# esp8266-rgb-ledstrip.net
KiCad netlist of a schematic drawn in EAGLE
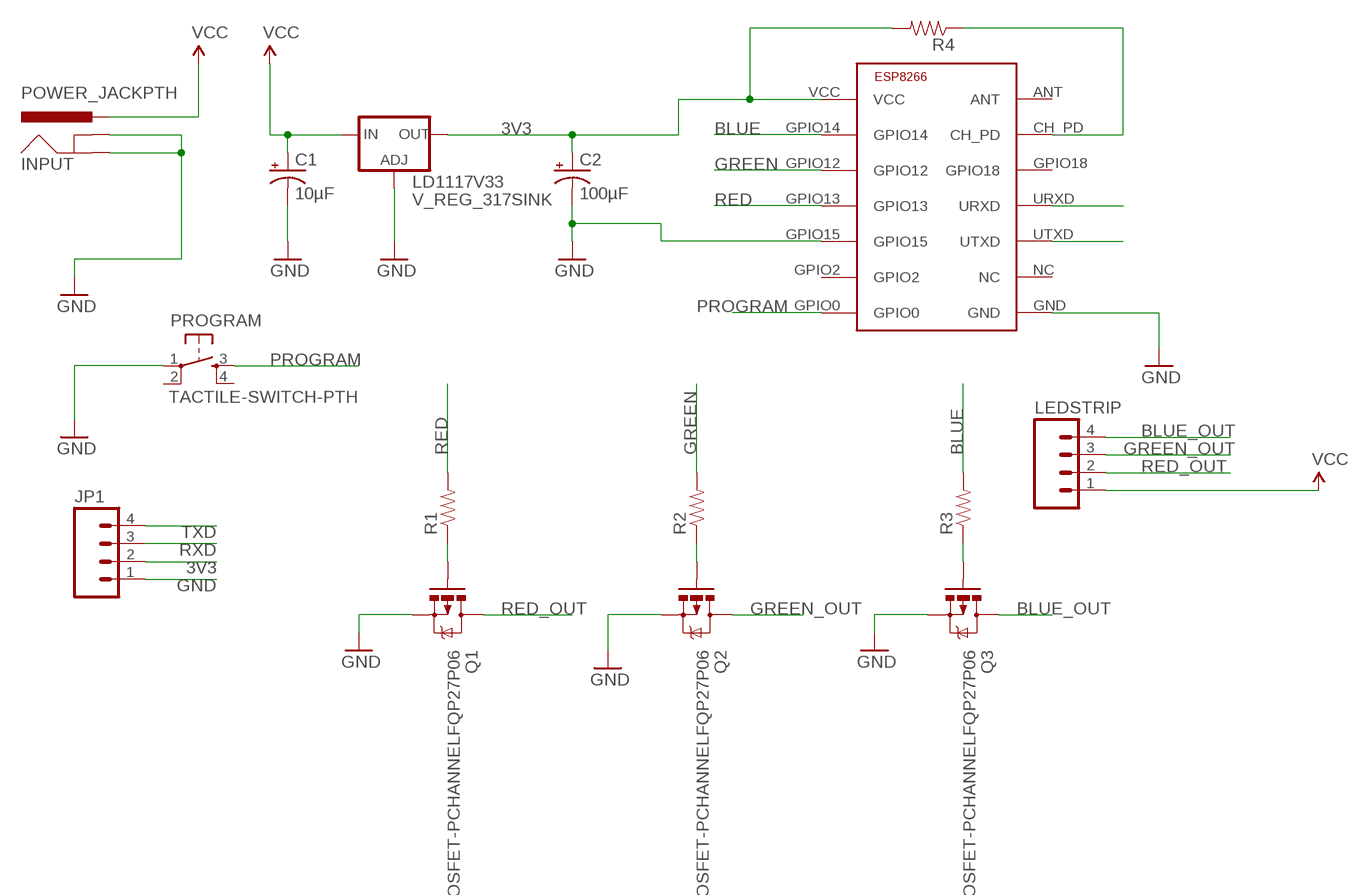
[diagram p0: schematic, sheet 1]

(export (version "E")
  (design (tool "Eeschema 10.0.6"))
  (components
    (comp (ref "C1")
      (value "10µF")
      (footprint "eagle-import:CPOL-RADIAL-10UF-25V")
      (libsource (lib "eagle-import") (part "CAP_POLPTH2"))
    )
    (comp (ref "C2")
      (value "100µF")
      (footprint "eagle-import:CPOL-RADIAL-100UF-25V")
      (libsource (lib "eagle-import") (part "CAP_POLPTH1"))
    )
    (comp (ref "INPUT")
      (value "POWER_JACKPTH")
      (footprint "eagle-import:POWER_JACK_PTH")
      (libsource (lib "eagle-import") (part "POWER_JACKPTH"))
    )
    (comp (ref "JP1")
      (value "M04PTH")
      (footprint "eagle-import:1X04")
      (libsource (lib "eagle-import") (part "M04PTH"))
    )
    (comp (ref "LD1117V33")
      (value "V_REG_317SINK")
      (footprint "eagle-import:TO220-ADJ")
      (libsource (lib "eagle-import") (part "V_REG_317SINK"))
    )
    (comp (ref "LEDSTRIP")
      (value "M04PTH")
      (footprint "eagle-import:1X04")
      (libsource (lib "eagle-import") (part "M04PTH"))
    )
    (comp (ref "PROGRAM")
      (value "TACTILE-SWITCH-PTH")
      (footprint "eagle-import:TAC-SWITCH-PTH")
      (libsource (lib "eagle-import") (part "TACTILE-SWITCH-PTH"))
    )
    (comp (ref "Q1")
      (value "MOSFET-PCHANNELFQP27P06")
      (footprint "eagle-import:TO220V")
      (libsource (lib "eagle-import") (part "MOSFET-PCHANNELFQP27P06"))
    )
    (comp (ref "Q2")
      (value "MOSFET-PCHANNELFQP27P06")
      (footprint "eagle-import:TO220V")
      (libsource (lib "eagle-import") (part "MOSFET-PCHANNELFQP27P06"))
    )
    (comp (ref "Q3")
      (value "MOSFET-PCHANNELFQP27P06")
      (footprint "eagle-import:TO220V")
      (libsource (lib "eagle-import") (part "MOSFET-PCHANNELFQP27P06"))
    )
    (comp (ref "R1")
      (value "RESISTORAXIAL-0.3")
      (footprint "eagle-import:AXIAL-0.3")
      (libsource (lib "eagle-import") (part "RESISTORAXIAL-0.3"))
    )
    (comp (ref "R2")
      (value "RESISTORAXIAL-0.3")
      (footprint "eagle-import:AXIAL-0.3")
      (libsource (lib "eagle-import") (part "RESISTORAXIAL-0.3"))
    )
    (comp (ref "R3")
      (value "RESISTORAXIAL-0.3")
      (footprint "eagle-import:AXIAL-0.3")
      (libsource (lib "eagle-import") (part "RESISTORAXIAL-0.3"))
    )
    (comp (ref "R4")
      (value "RESISTORAXIAL-0.3")
      (footprint "eagle-import:AXIAL-0.3")
      (libsource (lib "eagle-import") (part "RESISTORAXIAL-0.3"))
    )
    (comp (ref "U$1")
      (value "ESP8266-03")
      (footprint "eagle-import:ESP-03")
      (libsource (lib "eagle-import") (part "ESP8266-03"))
    )
  )
  (nets
    (net (code "1") (name "/3V3") (class "Default")
      (node (ref "C2") (pin "1") (pinfunction "+_1") (pintype "passive"))
      (node (ref "JP1") (pin "2") (pinfunction "2_2") (pintype "passive"))
      (node (ref "LD1117V33") (pin "OUT") (pinfunction "OUT_OUT") (pintype "output"))
      (node (ref "R4") (pin "P$2") (pinfunction "2_P$2") (pintype "passive"))
      (node (ref "U$1") (pin "VCC") (pinfunction "VCC_VCC") (pintype "bidirectional"))
    )
    (net (code "2") (name "/BLUE") (class "Default")
      (node (ref "R3") (pin "P$2") (pinfunction "2_P$2") (pintype "passive"))
      (node (ref "U$1") (pin "GPIO14") (pinfunction "GPIO14_GPIO14") (pintype "bidirectional"))
    )
    (net (code "3") (name "/BLUE_OUT") (class "Default")
      (node (ref "LEDSTRIP") (pin "4") (pinfunction "4_4") (pintype "passive"))
      (node (ref "Q3") (pin "2") (pinfunction "D_2") (pintype "passive"))
    )
    (net (code "4") (name "/GREEN") (class "Default")
      (node (ref "R2") (pin "P$2") (pinfunction "2_P$2") (pintype "passive"))
      (node (ref "U$1") (pin "GPIO12") (pinfunction "GPIO12_GPIO12") (pintype "bidirectional"))
    )
    (net (code "5") (name "/GREEN_OUT") (class "Default")
      (node (ref "LEDSTRIP") (pin "3") (pinfunction "3_3") (pintype "passive"))
      (node (ref "Q2") (pin "2") (pinfunction "D_2") (pintype "passive"))
    )
    (net (code "6") (name "/PROGRAM") (class "Default")
      (node (ref "PROGRAM") (pin "3") (pinfunction "3_3") (pintype "passive"))
      (node (ref "U$1") (pin "GPIO0") (pinfunction "GPIO0_GPIO0") (pintype "bidirectional"))
    )
    (net (code "7") (name "/RED") (class "Default")
      (node (ref "R1") (pin "P$2") (pinfunction "2_P$2") (pintype "passive"))
      (node (ref "U$1") (pin "GPIO13") (pinfunction "GPIO13_GPIO13") (pintype "bidirectional"))
    )
    (net (code "8") (name "/RED_OUT") (class "Default")
      (node (ref "LEDSTRIP") (pin "2") (pinfunction "2_2") (pintype "passive"))
      (node (ref "Q1") (pin "2") (pinfunction "D_2") (pintype "passive"))
    )
    (net (code "9") (name "/RXD") (class "Default")
      (node (ref "JP1") (pin "3") (pinfunction "3_3") (pintype "passive"))
      (node (ref "U$1") (pin "URXD") (pinfunction "URXD_URXD") (pintype "bidirectional"))
    )
    (net (code "10") (name "/TXD") (class "Default")
      (node (ref "JP1") (pin "4") (pinfunction "4_4") (pintype "passive"))
      (node (ref "U$1") (pin "UTXD") (pinfunction "UTXD_UTXD") (pintype "bidirectional"))
    )
    (net (code "11") (name "GND") (class "Default")
      (node (ref "C1") (pin "2") (pinfunction "-_2") (pintype "passive"))
      (node (ref "C2") (pin "2") (pinfunction "-_2") (pintype "passive"))
      (node (ref "INPUT") (pin "GND") (pinfunction "GND_GND") (pintype "bidirectional"))
      (node (ref "INPUT") (pin "GNDBREAK") (pinfunction "GNDBREAK_GNDBREAK") (pintype "bidirectional"))
      (node (ref "JP1") (pin "1") (pinfunction "1_1") (pintype "passive"))
      (node (ref "LD1117V33") (pin "ADJ") (pinfunction "ADJ_ADJ") (pintype "input"))
      (node (ref "PROGRAM") (pin "1") (pinfunction "1_1") (pintype "passive"))
      (node (ref "Q1") (pin "3") (pinfunction "S_3") (pintype "passive"))
      (node (ref "Q2") (pin "3") (pinfunction "S_3") (pintype "passive"))
      (node (ref "Q3") (pin "3") (pinfunction "S_3") (pintype "passive"))
      (node (ref "U$1") (pin "GND") (pinfunction "GND_GND") (pintype "bidirectional"))
      (node (ref "U$1") (pin "GPIO15") (pinfunction "GPIO15_GPIO15") (pintype "bidirectional"))
    )
    (net (code "12") (name "Net-(Q1-G)") (class "Default")
      (node (ref "Q1") (pin "1") (pinfunction "G_1") (pintype "passive"))
      (node (ref "R1") (pin "P$1") (pinfunction "1_P$1") (pintype "passive"))
    )
    (net (code "13") (name "Net-(Q2-G)") (class "Default")
      (node (ref "Q2") (pin "1") (pinfunction "G_1") (pintype "passive"))
      (node (ref "R2") (pin "P$1") (pinfunction "1_P$1") (pintype "passive"))
    )
    (net (code "14") (name "Net-(Q3-G)") (class "Default")
      (node (ref "Q3") (pin "1") (pinfunction "G_1") (pintype "passive"))
      (node (ref "R3") (pin "P$1") (pinfunction "1_P$1") (pintype "passive"))
    )
    (net (code "15") (name "Net-(R4-1)") (class "Default")
      (node (ref "R4") (pin "P$1") (pinfunction "1_P$1") (pintype "passive"))
      (node (ref "U$1") (pin "CH_PD") (pinfunction "CH_PD_CH_PD") (pintype "bidirectional"))
    )
    (net (code "16") (name "VCC") (class "Default")
      (node (ref "C1") (pin "1") (pinfunction "+_1") (pintype "passive"))
      (node (ref "INPUT") (pin "PWR") (pinfunction "PWR_PWR") (pintype "bidirectional"))
      (node (ref "LD1117V33") (pin "IN") (pinfunction "IN_IN") (pintype "input"))
      (node (ref "LEDSTRIP") (pin "1") (pinfunction "1_1") (pintype "passive"))
    )
    (net (code "17") (name "unconnected-(PROGRAM-Pad2)") (class "Default")
      (node (ref "PROGRAM") (pin "2") (pinfunction "2_2") (pintype "passive"))
    )
    (net (code "18") (name "unconnected-(PROGRAM-Pad4)") (class "Default")
      (node (ref "PROGRAM") (pin "4") (pinfunction "4_4") (pintype "passive"))
    )
    (net (code "19") (name "unconnected-(U$1-PadANT)") (class "Default")
      (node (ref "U$1") (pin "ANT") (pinfunction "ANT_ANT") (pintype "bidirectional"))
    )
    (net (code "20") (name "unconnected-(U$1-PadGPIO2)") (class "Default")
      (node (ref "U$1") (pin "GPIO2") (pinfunction "GPIO2_GPIO2") (pintype "bidirectional"))
    )
    (net (code "21") (name "unconnected-(U$1-PadGPIO18)") (class "Default")
      (node (ref "U$1") (pin "GPIO18") (pinfunction "GPIO18_GPIO18") (pintype "bidirectional"))
    )
    (net (code "22") (name "unconnected-(U$1-PadNC)") (class "Default")
      (node (ref "U$1") (pin "NC") (pinfunction "NC_NC") (pintype "bidirectional"))
    )
  )
)
